# 3_-_POWER.net
KiCad netlist of a schematic drawn in Altium Designer
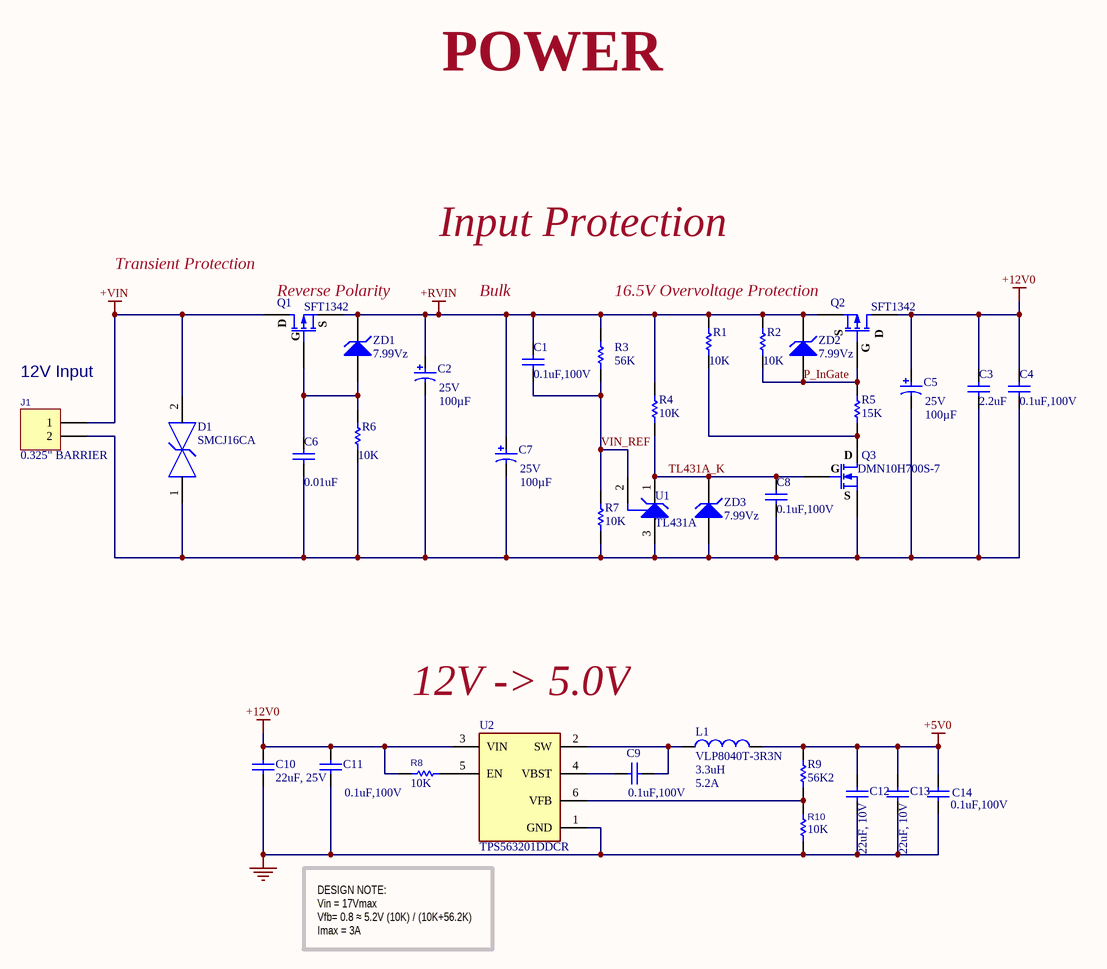
[diagram p0: [3] - POWER.SchDoc]

(export (version "E")
  (design (tool "Eeschema 10.0.6"))
  (components
    (comp (ref "C1")
      (value "0.1uF,100V")
      (footprint "C0805")
      (description "CAP CER 0.1UF 100V X7R 0805")
      (fields
        (field (name "MANUFACTURER") "Samsung")
        (field (name "MANUFACTURER PART NUMBER") "CL21B104KCFWPNE")
      )
      (libsource (lib "DVXC5 ECU") (part "CL21B104KCFWPNE"))
    )
    (comp (ref "C2")
      (value "EEEFK1E101XP")
      (footprint "PNSC-FK-V-D8_V")
      (fields
        (field (name "CAPACITANCE") "100µF")
        (field (name "MANUFACTURER") "Panasonic")
        (field (name "RATED VOLTAGE") "25V")
      )
      (libsource (lib "Altium Content Vault") (part "CAP-P-2"))
    )
    (comp (ref "C3")
      (value "2.2uF")
      (footprint "C1206")
      (description "CAP CER 1206 2.2UF 50V X7R 10%")
      (fields
        (field (name "MANUFACTURER") "KEMET")
        (field (name "MANUFACTURER PART NUMBER") "C1206C225K5RECAUTO")
      )
      (libsource (lib "DVXC5 ECU") (part "C1206C225K5RECAUTO"))
    )
    (comp (ref "C4")
      (value "0.1uF,100V")
      (footprint "C0805")
      (description "CAP CER 0.1UF 100V X7R 0805")
      (fields
        (field (name "MANUFACTURER") "Samsung")
        (field (name "MANUFACTURER PART NUMBER") "CL21B104KCFWPNE")
      )
      (libsource (lib "DVXC5 ECU") (part "CL21B104KCFWPNE"))
    )
    (comp (ref "C5")
      (value "EEEFK1E101XP")
      (footprint "PNSC-FK-V-D8_V")
      (fields
        (field (name "CAPACITANCE") "100µF")
        (field (name "MANUFACTURER") "Panasonic")
        (field (name "RATED VOLTAGE") "25V")
      )
      (libsource (lib "Altium Content Vault") (part "CAP-P-2"))
    )
    (comp (ref "C6")
      (value "0.01uF")
      (footprint "C0603")
      (description "Cap Ceramic 0.01uF 50V X7R 5% Pad SMD 0603 125C Automotive T/R")
      (fields
        (field (name "MANUFACTURER") "KEMET")
        (field (name "MANUFACTURER PART NUMBER") "C0603C103J5RACAUTO")
      )
      (libsource (lib "DVXC5 ECU") (part "C0603C103J5RACAUTO"))
    )
    (comp (ref "C7")
      (value "EEEFK1E101XP")
      (footprint "PNSC-FK-V-D8_V")
      (fields
        (field (name "CAPACITANCE") "100µF")
        (field (name "MANUFACTURER") "Panasonic")
        (field (name "RATED VOLTAGE") "25V")
      )
      (libsource (lib "Altium Content Vault") (part "CAP-P-2"))
    )
    (comp (ref "C8")
      (value "0.1uF,100V")
      (footprint "C0805")
      (description "CAP CER 0.1UF 100V X7R 0805")
      (fields
        (field (name "MANUFACTURER") "Samsung")
        (field (name "MANUFACTURER PART NUMBER") "CL21B104KCFWPNE")
      )
      (libsource (lib "DVXC5 ECU") (part "CL21B104KCFWPNE"))
    )
    (comp (ref "C9")
      (value "0.1uF,100V")
      (footprint "C0805")
      (description "CAP CER 0.1UF 100V X7R 0805")
      (fields
        (field (name "MANUFACTURER") "Samsung")
        (field (name "MANUFACTURER PART NUMBER") "CL21B104KCFWPNE")
      )
      (libsource (lib "DVXC5 ECU") (part "CL21B104KCFWPNE"))
    )
    (comp (ref "C10")
      (value "22uF, 25V")
      (footprint "C1210")
      (description "22µF ±20% 25V Ceramic Capacitor X7R 1210 (3225 Metric)")
      (fields
        (field (name "MANUFACTURER") "Taiyo Yuden")
        (field (name "MANUFACTURER PART NUMBER") "TMK325B7226MMHP")
      )
      (libsource (lib "DVXC4+ ECU (2)") (part "TMK325B7226MMHP"))
    )
    (comp (ref "C11")
      (value "0.1uF,100V")
      (footprint "C0805")
      (description "CAP CER 0.1UF 100V X7R 0805")
      (fields
        (field (name "MANUFACTURER") "Samsung")
        (field (name "MANUFACTURER PART NUMBER") "CL21B104KCFWPNE")
      )
      (libsource (lib "DVXC5 ECU") (part "CL21B104KCFWPNE"))
    )
    (comp (ref "C12")
      (value "22uF, 10V")
      (footprint "C0805")
      (description "MURATA - GRM21BR61A226ME51L - CAP, MLCC, X5R, 22UF, 10V, 0805")
      (fields
        (field (name "MANUFACTURER") "Murata")
        (field (name "MANUFACTURER PART NUMBER") "GRM21BR61A226ME51L")
      )
      (libsource (lib "DVXC4+ ECU (2)") (part "GRM21BR61A226ME51L"))
    )
    (comp (ref "C13")
      (value "22uF, 10V")
      (footprint "C0805")
      (description "MURATA - GRM21BR61A226ME51L - CAP, MLCC, X5R, 22UF, 10V, 0805")
      (fields
        (field (name "MANUFACTURER") "Murata")
        (field (name "MANUFACTURER PART NUMBER") "GRM21BR61A226ME51L")
      )
      (libsource (lib "DVXC4+ ECU (2)") (part "GRM21BR61A226ME51L"))
    )
    (comp (ref "C14")
      (value "0.1uF,100V")
      (footprint "C0805")
      (description "CAP CER 0.1UF 100V X7R 0805")
      (fields
        (field (name "MANUFACTURER") "Samsung")
        (field (name "MANUFACTURER PART NUMBER") "CL21B104KCFWPNE")
      )
      (libsource (lib "DVXC5 ECU") (part "CL21B104KCFWPNE"))
    )
    (comp (ref "D1")
      (value "SMCJ16CA")
      (footprint "FP-SMBJ-MFG")
      (description "TVS DIODE 18V 29.2V DO214AA")
      (fields
        (field (name "MANUFACTURER PART NUMBER") "SMCJ18CA")
        (field (name "MANUFACTURER") "Littelfuse Inc")
      )
      (libsource (lib "Altium Content Vault") (part "876f4347bf90aa6f500f43e3cd03972"))
    )
    (comp (ref "J1")
      (value "0.325\" BARRIER")
      (footprint "Barrier2")
      (description "CONN BARRIER STRIP 2CIRC 0.325\"")
      (fields
        (field (name "MANUFACTURER") "On-Shore Technology")
        (field (name "MANUFACTURER PART NUMBER") "OSTYK42102030")
      )
      (libsource (lib "7_DAY_TIMER") (part "OSTYK42102030"))
    )
    (comp (ref "L1")
      (value "VLP8040T-3R3N")
      (description "FIXED IND 3.3UH 5.2A 20 MOHM SMD")
      (fields
        (field (name "MANUFACTURER") "TDK")
        (field (name "TOLERANCE") "30%")
        (field (name "INDUCTANCE") "3.3uH")
        (field (name "RMS CURRENT (IRMS)") "5.2A")
      )
      (libsource (lib "DVXC4+ ECU (2)") (part "VLP8040T-3R3N"))
    )
    (comp (ref "Q1")
      (value "SFT1342")
      (description "MOSFET P-CH 60V 12A TP-FA")
      (fields
        (field (name "MANUFACTURER") "ON Semiconductor")
        (field (name "MANUFACTURER PART NUMBER") "SFT1342-TL-W")
      )
      (libsource (lib "DVXC5 ECU") (part "SFT1342-TL-W"))
    )
    (comp (ref "Q2")
      (value "SFT1342")
      (description "MOSFET P-CH 60V 12A TP-FA")
      (fields
        (field (name "MANUFACTURER") "ON Semiconductor")
        (field (name "MANUFACTURER PART NUMBER") "SFT1342-TL-W")
      )
      (libsource (lib "DVXC5 ECU") (part "SFT1342-TL-W"))
    )
    (comp (ref "Q3")
      (value "DMN10H700S-7")
      (footprint "SOT90P240X110-3N")
      (description "MOSFET N-CHA 100V 700MA SOT23")
      (fields (field (name "MANUFACTURER") "Diodes"))
      (libsource (lib "DVXC5 ECU") (part "DMN10H700S-7"))
    )
    (comp (ref "R1")
      (value "10K")
      (footprint "R0603")
      (description "RES 10K OHM 1% 1/10W 0603")
      (fields
        (field (name "MANUFACTURER") "Stackpole Electronics")
        (field (name "MANUFACTURER PART NUMBER") "RMCF0603FT10K0")
      )
      (libsource (lib "DVXC5 ECU") (part "RMCF0603FT10K0"))
    )
    (comp (ref "R2")
      (value "10K")
      (footprint "R0603")
      (description "RES 10K OHM 1% 1/10W 0603")
      (fields
        (field (name "MANUFACTURER") "Stackpole Electronics")
        (field (name "MANUFACTURER PART NUMBER") "RMCF0603FT10K0")
      )
      (libsource (lib "DVXC5 ECU") (part "RMCF0603FT10K0"))
    )
    (comp (ref "R3")
      (value "56K")
      (footprint "RESC1608X55X30ML15T15")
      (fields (field (name "PART NUMBER") "ERJ3EKF5602V") (field (name "MANUFACTURER") "Panasonic"))
      (libsource (lib "Altium Content Vault") (part "RES"))
    )
    (comp (ref "R4")
      (value "10K")
      (footprint "R0603")
      (description "RES 10K OHM 1% 1/10W 0603")
      (fields
        (field (name "MANUFACTURER") "Stackpole Electronics")
        (field (name "MANUFACTURER PART NUMBER") "RMCF0603FT10K0")
      )
      (libsource (lib "DVXC5 ECU") (part "RMCF0603FT10K0"))
    )
    (comp (ref "R5")
      (value "15K")
      (footprint "R0603")
      (description "RES 15K OHM 1% 1/10W 0603")
      (fields
        (field (name "MANUFACTURER") "Stackpole Electronics")
        (field (name "MANUFACTURER PART NUMBER") "RMCF0603FT15K0")
      )
      (libsource (lib "DVXC5 ECU") (part "RMCF0603FT15K0"))
    )
    (comp (ref "R6")
      (value "10K")
      (footprint "R0603")
      (description "RES 10K OHM 1% 1/10W 0603")
      (fields
        (field (name "MANUFACTURER") "Stackpole Electronics")
        (field (name "MANUFACTURER PART NUMBER") "RMCF0603FT10K0")
      )
      (libsource (lib "DVXC5 ECU") (part "RMCF0603FT10K0"))
    )
    (comp (ref "R7")
      (value "10K")
      (footprint "R0603")
      (description "RES 10K OHM 1% 1/10W 0603")
      (fields
        (field (name "MANUFACTURER") "Stackpole Electronics")
        (field (name "MANUFACTURER PART NUMBER") "RMCF0603FT10K0")
      )
      (libsource (lib "DVXC5 ECU") (part "RMCF0603FT10K0"))
    )
    (comp (ref "R8")
      (value "10K")
      (footprint "R0402")
      (description "RES 10K OHM 1% 1/16W 0402")
      (fields
        (field (name "MANUFACTURER") "Stackpole Electronics")
        (field (name "MANUFACTURER PART NUMBER") "RMCF0402FT10K0")
      )
      (libsource (lib "DVXC4+ ECU (2)") (part "RMCF0402FT10K0"))
    )
    (comp (ref "R9")
      (value "56K2")
      (footprint "r0402")
      (description "Res Thick Film 0402 56.2K Ohm 1% 0.063W ±100ppm/°C Molded SMD Paper T/R")
      (fields
        (field (name "MANUFACTURER") "Stackpole Electronics")
        (field (name "MANUFACTURER PART NUMBER") "RMCF0402FT56K2")
      )
      (libsource (lib "DVXC4+ ECU (2)") (part "RMCF0402FT56K2"))
    )
    (comp (ref "R10")
      (value "10K")
      (footprint "R0402")
      (description "RES 10K OHM 1% 1/16W 0402")
      (fields
        (field (name "MANUFACTURER") "Stackpole Electronics")
        (field (name "MANUFACTURER PART NUMBER") "RMCF0402FT10K0")
      )
      (libsource (lib "DVXC4+ ECU (2)") (part "RMCF0402FT10K0"))
    )
    (comp (ref "U1")
      (value "TL431A")
      (footprint "TL431AQDBZRQ1")
      (description "IC VREF SHUNT ADJ SOT23-3")
      (fields
        (field (name "MANUFACTURER") "Texas Instruments")
        (field (name "MANUFACTURER PART NUMBER") "TL431AQDBZRQ1")
      )
      (libsource (lib "DVXC5 ECU") (part "TL431AQDBZRQ1"))
    )
    (comp (ref "U2")
      (value "TPS563201DDCR")
      (description "IC REG BUCK ADJ 3A TSOT23-6")
      (fields (field (name "MANUFACTURER") "Texas Instruments"))
      (libsource (lib "DVXC4+ ECU (2)") (part "TPS563201DDCR"))
    )
    (comp (ref "ZD1")
      (value "7.99Vz")
      (description "Zener Diode Microsmf Do-219Ac")
      (fields (field (name "MANUFACTURER") "Vishay") (field (name "MANUFACTURER PART NUMBER") "PLZ8V2B-G3/H"))
      (libsource (lib "DVXC5 ECU") (part "PLZ8V2B-G3/H"))
    )
    (comp (ref "ZD2")
      (value "7.99Vz")
      (description "Zener Diode Microsmf Do-219Ac")
      (fields (field (name "MANUFACTURER") "Vishay") (field (name "MANUFACTURER PART NUMBER") "PLZ8V2B-G3/H"))
      (libsource (lib "DVXC5 ECU") (part "PLZ8V2B-G3/H"))
    )
    (comp (ref "ZD3")
      (value "7.99Vz")
      (description "Zener Diode Microsmf Do-219Ac")
      (fields (field (name "MANUFACTURER") "Vishay") (field (name "MANUFACTURER PART NUMBER") "PLZ8V2B-G3/H"))
      (libsource (lib "DVXC5 ECU") (part "PLZ8V2B-G3/H"))
    )
  )
  (nets
    (net (code "1") (name "+5V0") (class "Default")
      (node (ref "C12") (pin "2") (pinfunction "2_2") (pintype "passive"))
      (node (ref "C13") (pin "2") (pinfunction "2_2") (pintype "passive"))
      (node (ref "C14") (pin "1") (pinfunction "1_1") (pintype "passive"))
      (node (ref "L1") (pin "2") (pinfunction "2_2") (pintype "passive"))
      (node (ref "R9") (pin "2") (pinfunction "2_2") (pintype "passive"))
    )
    (net (code "2") (name "+12V0") (class "Default")
      (node (ref "C10") (pin "2") (pinfunction "2_2") (pintype "passive"))
      (node (ref "C11") (pin "2") (pinfunction "2_2") (pintype "passive"))
      (node (ref "C3") (pin "2") (pinfunction "2_2") (pintype "passive"))
      (node (ref "C4") (pin "2") (pinfunction "2_2") (pintype "passive"))
      (node (ref "C5") (pin "1") (pinfunction "1_1") (pintype "passive"))
      (node (ref "Q2") (pin "1") (pinfunction "D_1") (pintype "passive"))
      (node (ref "R8") (pin "1") (pinfunction "1_1") (pintype "passive"))
      (node (ref "U2") (pin "3") (pinfunction "VIN_3") (pintype "passive"))
    )
    (net (code "3") (name "+RVIN") (class "Default")
      (node (ref "C1") (pin "2") (pinfunction "2_2") (pintype "passive"))
      (node (ref "C2") (pin "1") (pinfunction "1_1") (pintype "passive"))
      (node (ref "C7") (pin "1") (pinfunction "1_1") (pintype "passive"))
      (node (ref "Q1") (pin "3") (pinfunction "S_3") (pintype "passive"))
      (node (ref "Q2") (pin "3") (pinfunction "S_3") (pintype "passive"))
      (node (ref "R1") (pin "2") (pinfunction "2_2") (pintype "passive"))
      (node (ref "R2") (pin "2") (pinfunction "2_2") (pintype "passive"))
      (node (ref "R3") (pin "2") (pinfunction "2_2") (pintype "passive"))
      (node (ref "R4") (pin "2") (pinfunction "2_2") (pintype "passive"))
      (node (ref "ZD1") (pin "2") (pinfunction "K_2") (pintype "passive"))
      (node (ref "ZD2") (pin "2") (pinfunction "K_2") (pintype "passive"))
    )
    (net (code "4") (name "+VIN") (class "Default")
      (node (ref "D1") (pin "2") (pinfunction "2_2") (pintype "passive"))
      (node (ref "J1") (pin "1") (pinfunction "1_1") (pintype "passive"))
      (node (ref "Q1") (pin "1") (pinfunction "D_1") (pintype "passive"))
    )
    (net (code "5") (name "/P_InGate") (class "Default")
      (node (ref "Q2") (pin "2") (pinfunction "G_2") (pintype "passive"))
      (node (ref "R2") (pin "1") (pinfunction "1_1") (pintype "passive"))
      (node (ref "R5") (pin "2") (pinfunction "2_2") (pintype "passive"))
      (node (ref "ZD2") (pin "1") (pinfunction "A_1") (pintype "passive"))
    )
    (net (code "6") (name "/TL431A_K") (class "Default")
      (node (ref "C8") (pin "2") (pinfunction "2_2") (pintype "passive"))
      (node (ref "Q3") (pin "1") (pinfunction "G_1") (pintype "passive"))
      (node (ref "R4") (pin "1") (pinfunction "1_1") (pintype "passive"))
      (node (ref "U1") (pin "1") (pinfunction "CATHODE_1") (pintype "passive"))
      (node (ref "ZD3") (pin "2") (pinfunction "K_2") (pintype "passive"))
    )
    (net (code "7") (name "/VIN_REF") (class "Default")
      (node (ref "C1") (pin "1") (pinfunction "1_1") (pintype "passive"))
      (node (ref "R3") (pin "1") (pinfunction "1_1") (pintype "passive"))
      (node (ref "R7") (pin "2") (pinfunction "2_2") (pintype "passive"))
      (node (ref "U1") (pin "2") (pinfunction "REF_2") (pintype "passive"))
    )
    (net (code "8") (name "GND") (class "Default")
      (node (ref "C10") (pin "1") (pinfunction "1_1") (pintype "passive"))
      (node (ref "C11") (pin "1") (pinfunction "1_1") (pintype "passive"))
      (node (ref "C12") (pin "1") (pinfunction "1_1") (pintype "passive"))
      (node (ref "C13") (pin "1") (pinfunction "1_1") (pintype "passive"))
      (node (ref "C14") (pin "2") (pinfunction "2_2") (pintype "passive"))
      (node (ref "R10") (pin "1") (pinfunction "1_1") (pintype "passive"))
      (node (ref "U2") (pin "1") (pinfunction "GND_1") (pintype "passive"))
    )
    (net (code "9") (name "Net-(Q1-G)") (class "Default")
      (node (ref "C6") (pin "2") (pinfunction "2_2") (pintype "passive"))
      (node (ref "Q1") (pin "2") (pinfunction "G_2") (pintype "passive"))
      (node (ref "R6") (pin "2") (pinfunction "2_2") (pintype "passive"))
      (node (ref "ZD1") (pin "1") (pinfunction "A_1") (pintype "passive"))
    )
    (net (code "10") (name "Net-(Q3-D)") (class "Default")
      (node (ref "Q3") (pin "3") (pinfunction "D_3") (pintype "passive"))
      (node (ref "R1") (pin "1") (pinfunction "1_1") (pintype "passive"))
      (node (ref "R5") (pin "1") (pinfunction "1_1") (pintype "passive"))
    )
    (net (code "11") (name "Net-(Q3-S)") (class "Default")
      (node (ref "C2") (pin "2") (pinfunction "2_2") (pintype "passive"))
      (node (ref "C3") (pin "1") (pinfunction "1_1") (pintype "passive"))
      (node (ref "C4") (pin "1") (pinfunction "1_1") (pintype "passive"))
      (node (ref "C5") (pin "2") (pinfunction "2_2") (pintype "passive"))
      (node (ref "C6") (pin "1") (pinfunction "1_1") (pintype "passive"))
      (node (ref "C7") (pin "2") (pinfunction "2_2") (pintype "passive"))
      (node (ref "C8") (pin "1") (pinfunction "1_1") (pintype "passive"))
      (node (ref "D1") (pin "1") (pinfunction "1_1") (pintype "passive"))
      (node (ref "J1") (pin "2") (pinfunction "2_2") (pintype "passive"))
      (node (ref "Q3") (pin "2") (pinfunction "S_2") (pintype "passive"))
      (node (ref "R6") (pin "1") (pinfunction "1_1") (pintype "passive"))
      (node (ref "R7") (pin "1") (pinfunction "1_1") (pintype "passive"))
      (node (ref "U1") (pin "3") (pinfunction "ANODE_3") (pintype "power_in"))
      (node (ref "ZD3") (pin "1") (pinfunction "A_1") (pintype "passive"))
    )
    (net (code "12") (name "Net-(U2-EN)") (class "Default")
      (node (ref "R8") (pin "2") (pinfunction "2_2") (pintype "passive"))
      (node (ref "U2") (pin "5") (pinfunction "EN_5") (pintype "passive"))
    )
    (net (code "13") (name "Net-(U2-SW)") (class "Default")
      (node (ref "C9") (pin "1") (pinfunction "1_1") (pintype "passive"))
      (node (ref "L1") (pin "1") (pinfunction "1_1") (pintype "passive"))
      (node (ref "U2") (pin "2") (pinfunction "SW_2") (pintype "passive"))
    )
    (net (code "14") (name "Net-(U2-VBST)") (class "Default")
      (node (ref "C9") (pin "2") (pinfunction "2_2") (pintype "passive"))
      (node (ref "U2") (pin "4") (pinfunction "VBST_4") (pintype "passive"))
    )
    (net (code "15") (name "Net-(U2-VFB)") (class "Default")
      (node (ref "R10") (pin "2") (pinfunction "2_2") (pintype "passive"))
      (node (ref "R9") (pin "1") (pinfunction "1_1") (pintype "passive"))
      (node (ref "U2") (pin "6") (pinfunction "VFB_6") (pintype "passive"))
    )
  )
)
